# RedBot_Mechanical_Bumper.net
KiCad netlist of a schematic drawn in EAGLE
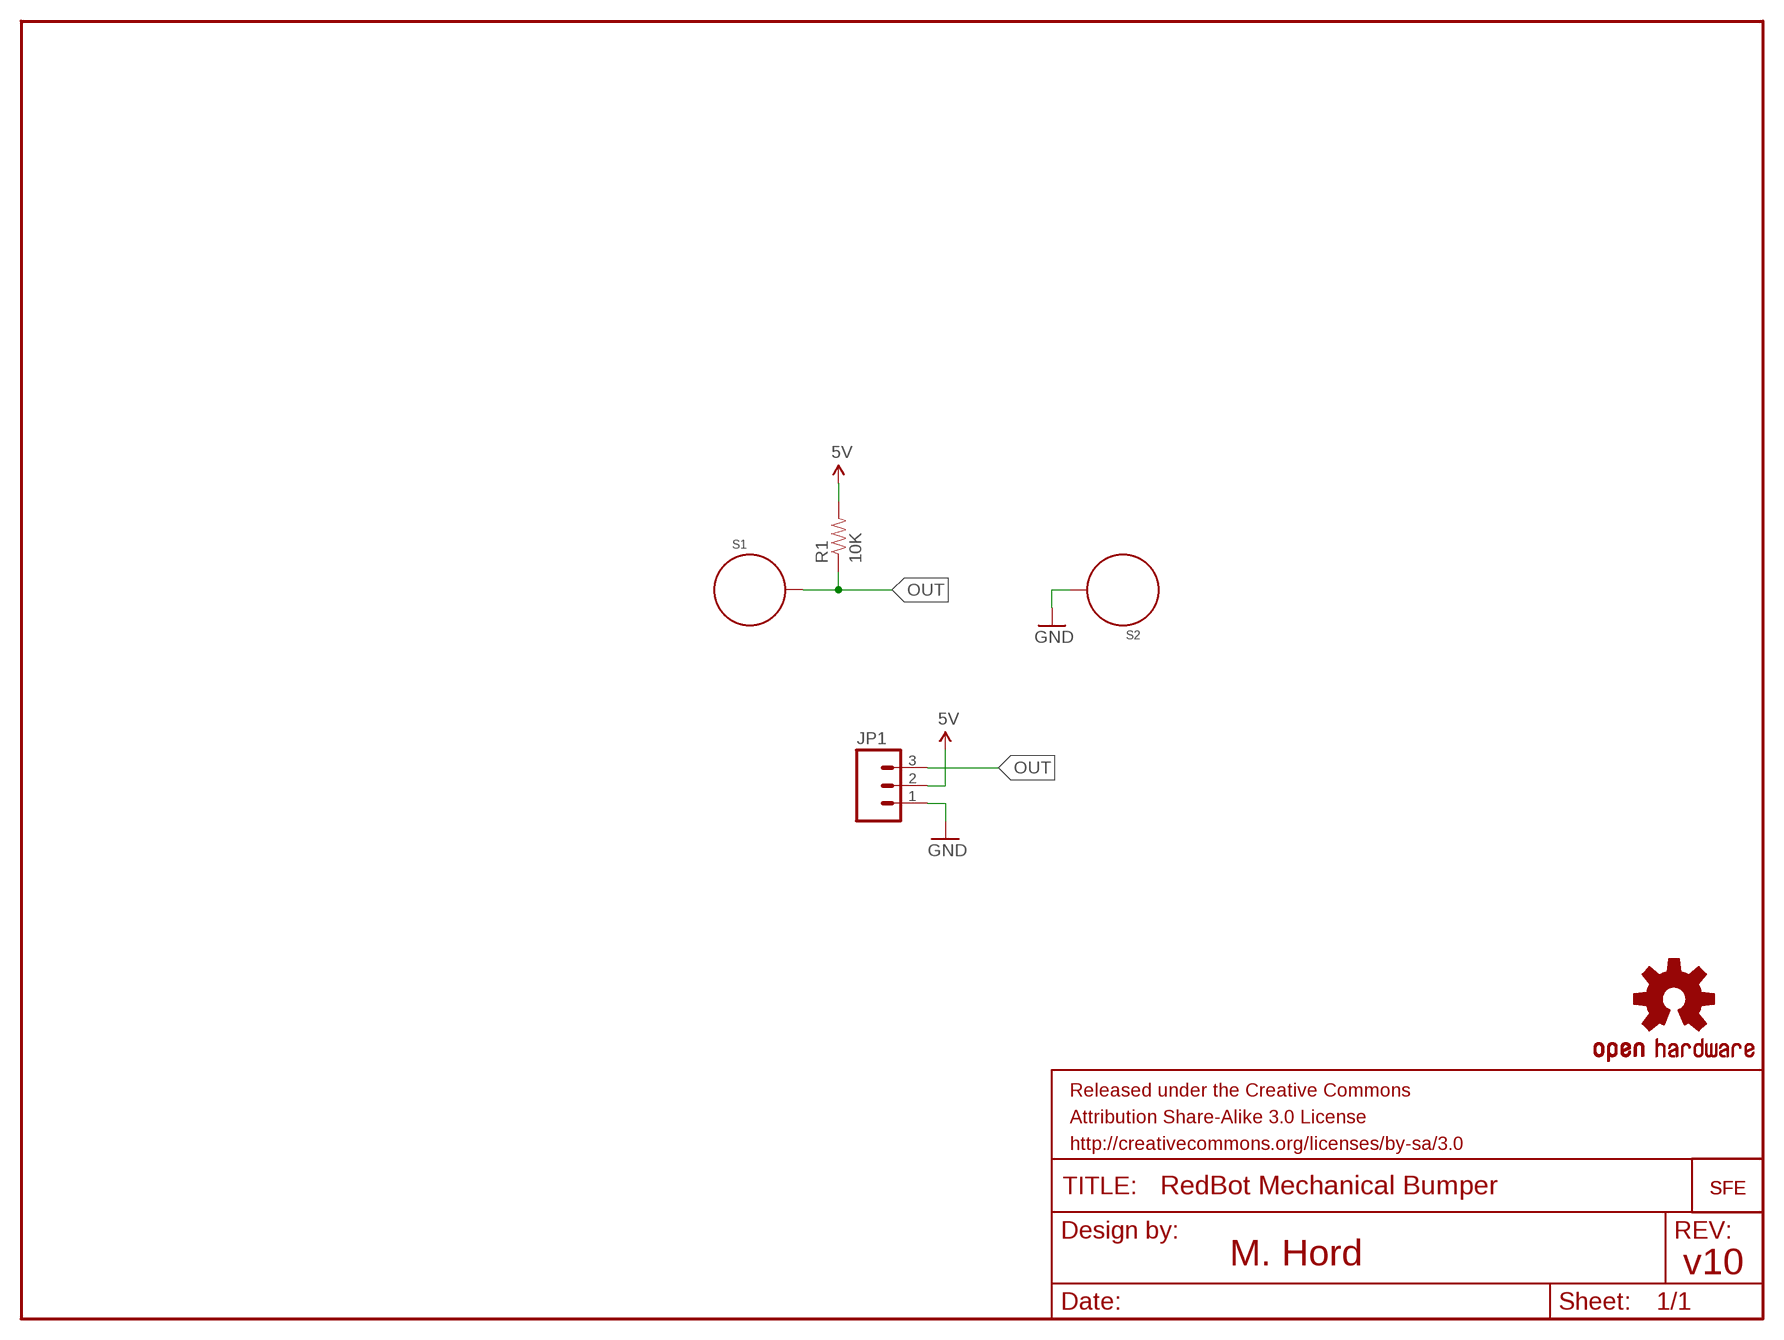
[diagram p0: schematic, sheet 1]

(export (version "E")
  (design (tool "Eeschema 10.0.6"))
  (components
    (comp (ref "FRAME1")
      (value "FRAME-LETTER")
      (footprint "eagle-import:CREATIVE_COMMONS")
      (libsource (lib "eagle-import") (part "FRAME-LETTER"))
    )
    (comp (ref "JP1")
      (value "M03SMD_RA_MALE")
      (footprint "eagle-import:1X03_SMD_RA_MALE")
      (libsource (lib "eagle-import") (part "M03SMD_RA_MALE"))
    )
    (comp (ref "LOGO1")
      (value "OSHW-LOGOS")
      (footprint "eagle-import:OSHW-LOGO-S")
      (libsource (lib "eagle-import") (part "OSHW-LOGOS"))
    )
    (comp (ref "LOGO2")
      (value "LOGO-SFESK")
      (footprint "eagle-import:SFE-LOGO-FLAME")
      (libsource (lib "eagle-import") (part "LOGO-SFESK"))
    )
    (comp (ref "LOGO3")
      (value "OSHW-LOGOS")
      (footprint "eagle-import:OSHW-LOGO-S")
      (libsource (lib "eagle-import") (part "OSHW-LOGOS"))
    )
    (comp (ref "LOGO4")
      (value "LOGO-SFESK")
      (footprint "eagle-import:SFE-LOGO-FLAME")
      (libsource (lib "eagle-import") (part "LOGO-SFESK"))
    )
    (comp (ref "R1")
      (value "10K")
      (footprint "eagle-import:0603-RES")
      (libsource (lib "eagle-import") (part "10KOHM1/10W1%(0603)0603"))
    )
    (comp (ref "S1")
      (value "STANDOFF_ELECTRICAL")
      (footprint "eagle-import:STANDOFF-ELECTRICAL")
      (libsource (lib "eagle-import") (part "STANDOFF_ELECTRICAL"))
    )
    (comp (ref "S2")
      (value "STANDOFF_ELECTRICAL")
      (footprint "eagle-import:STANDOFF-ELECTRICAL")
      (libsource (lib "eagle-import") (part "STANDOFF_ELECTRICAL"))
    )
  )
  (nets
    (net (code "1") (name "5V") (class "Default")
      (node (ref "JP1") (pin "2") (pinfunction "2_2") (pintype "passive"))
      (node (ref "R1") (pin "2") (pinfunction "2_2") (pintype "passive"))
    )
    (net (code "2") (name "GND") (class "Default")
      (node (ref "JP1") (pin "1") (pinfunction "1_1") (pintype "passive"))
      (node (ref "S2") (pin "P1") (pinfunction "P$1_P1") (pintype "bidirectional"))
    )
    (net (code "3") (name "OUT") (class "Default")
      (node (ref "JP1") (pin "3") (pinfunction "3_3") (pintype "passive"))
      (node (ref "R1") (pin "1") (pinfunction "1_1") (pintype "passive"))
      (node (ref "S1") (pin "P1") (pinfunction "P$1_P1") (pintype "bidirectional"))
    )
  )
)
